# Schematic-20pin.net
KiCad netlist of a schematic drawn in Altium Designer
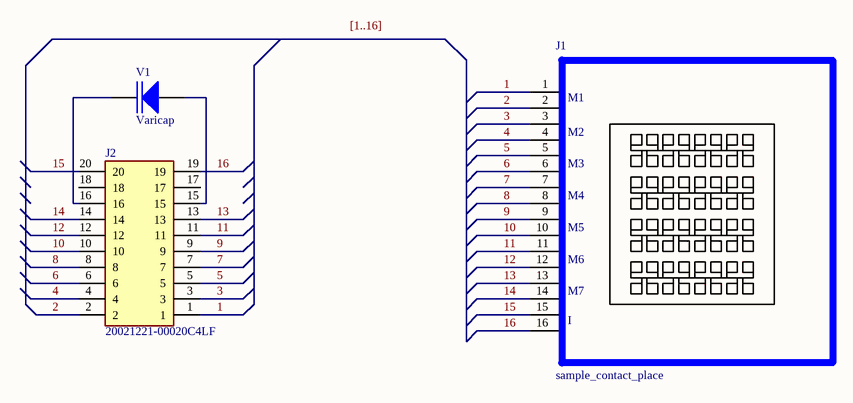
[diagram p0: Schematic-20pin.SchDoc]

(export (version "E")
  (design (tool "Eeschema 10.0.6"))
  (components
    (comp (ref "J1")
      (value "sample_contact_place")
      (footprint "sample")
      (libsource (lib "sample_holder_library") (part "sample_contact_place"))
    )
    (comp (ref "J2")
      (value "20021221-00020C4LF")
      (footprint "2002122100020C4LF")
      (description "Connector")
      (libsource (lib "sample_holder_library") (part "20021221-00020C4LF"))
    )
    (comp (ref "V1")
      (value "Varicap")
      (footprint "DIOC160X80X70L20N")
      (libsource (lib "sample_holder_library") (part "Varicap"))
    )
  )
  (nets
    (net (code "1") (name "/1") (class "Default")
      (node (ref "J1") (pin "1") (pinfunction "1_1") (pintype "passive"))
      (node (ref "J2") (pin "1") (pinfunction "1_1") (pintype "passive"))
    )
    (net (code "2") (name "/2") (class "Default")
      (node (ref "J1") (pin "2") (pinfunction "2_2") (pintype "passive"))
      (node (ref "J2") (pin "2") (pinfunction "2_2") (pintype "passive"))
    )
    (net (code "3") (name "/3") (class "Default")
      (node (ref "J1") (pin "3") (pinfunction "3_3") (pintype "passive"))
      (node (ref "J2") (pin "3") (pinfunction "3_3") (pintype "passive"))
    )
    (net (code "4") (name "/4") (class "Default")
      (node (ref "J1") (pin "4") (pinfunction "4_4") (pintype "passive"))
      (node (ref "J2") (pin "4") (pinfunction "4_4") (pintype "passive"))
    )
    (net (code "5") (name "/5") (class "Default")
      (node (ref "J1") (pin "5") (pinfunction "5_5") (pintype "passive"))
      (node (ref "J2") (pin "5") (pinfunction "5_5") (pintype "passive"))
    )
    (net (code "6") (name "/6") (class "Default")
      (node (ref "J1") (pin "6") (pinfunction "6_6") (pintype "passive"))
      (node (ref "J2") (pin "6") (pinfunction "6_6") (pintype "passive"))
    )
    (net (code "7") (name "/7") (class "Default")
      (node (ref "J1") (pin "7") (pinfunction "7_7") (pintype "passive"))
      (node (ref "J2") (pin "7") (pinfunction "7_7") (pintype "passive"))
    )
    (net (code "8") (name "/8") (class "Default")
      (node (ref "J1") (pin "8") (pinfunction "8_8") (pintype "passive"))
      (node (ref "J2") (pin "8") (pinfunction "8_8") (pintype "passive"))
    )
    (net (code "9") (name "/9") (class "Default")
      (node (ref "J1") (pin "9") (pinfunction "9_9") (pintype "passive"))
      (node (ref "J2") (pin "9") (pinfunction "9_9") (pintype "passive"))
    )
    (net (code "10") (name "/10") (class "Default")
      (node (ref "J1") (pin "10") (pinfunction "10_10") (pintype "passive"))
      (node (ref "J2") (pin "10") (pinfunction "10_10") (pintype "passive"))
    )
    (net (code "11") (name "/11") (class "Default")
      (node (ref "J1") (pin "11") (pinfunction "11_11") (pintype "passive"))
      (node (ref "J2") (pin "11") (pinfunction "11_11") (pintype "passive"))
    )
    (net (code "12") (name "/12") (class "Default")
      (node (ref "J1") (pin "12") (pinfunction "12_12") (pintype "passive"))
      (node (ref "J2") (pin "12") (pinfunction "12_12") (pintype "passive"))
    )
    (net (code "13") (name "/13") (class "Default")
      (node (ref "J1") (pin "13") (pinfunction "13_13") (pintype "passive"))
      (node (ref "J2") (pin "13") (pinfunction "13_13") (pintype "passive"))
    )
    (net (code "14") (name "/14") (class "Default")
      (node (ref "J1") (pin "14") (pinfunction "14_14") (pintype "passive"))
      (node (ref "J2") (pin "14") (pinfunction "14_14") (pintype "passive"))
    )
    (net (code "15") (name "/15") (class "Default")
      (node (ref "J1") (pin "15") (pinfunction "15_15") (pintype "passive"))
      (node (ref "J2") (pin "20") (pinfunction "20_20") (pintype "passive"))
    )
    (net (code "16") (name "/16") (class "Default")
      (node (ref "J1") (pin "16") (pinfunction "16_16") (pintype "passive"))
      (node (ref "J2") (pin "19") (pinfunction "19_19") (pintype "passive"))
    )
    (net (code "18") (name "Net-(J2-Pad15)") (class "Default")
      (node (ref "J2") (pin "15") (pinfunction "15_15") (pintype "passive"))
      (node (ref "V1") (pin "A") (pinfunction "A_A") (pintype "passive"))
    )
    (net (code "19") (name "Net-(J2-Pad16)") (class "Default")
      (node (ref "J2") (pin "16") (pinfunction "16_16") (pintype "passive"))
      (node (ref "V1") (pin "C") (pinfunction "C_C") (pintype "passive"))
    )
    (net (code "20") (name "unconnected-(J2-Pad17)") (class "Default")
      (node (ref "J2") (pin "17") (pinfunction "17_17") (pintype "passive"))
    )
    (net (code "21") (name "unconnected-(J2-Pad18)") (class "Default")
      (node (ref "J2") (pin "18") (pinfunction "18_18") (pintype "passive"))
    )
  )
)
